# lego-traffic-lights-controller.net
KiCad netlist of a schematic drawn in EAGLE
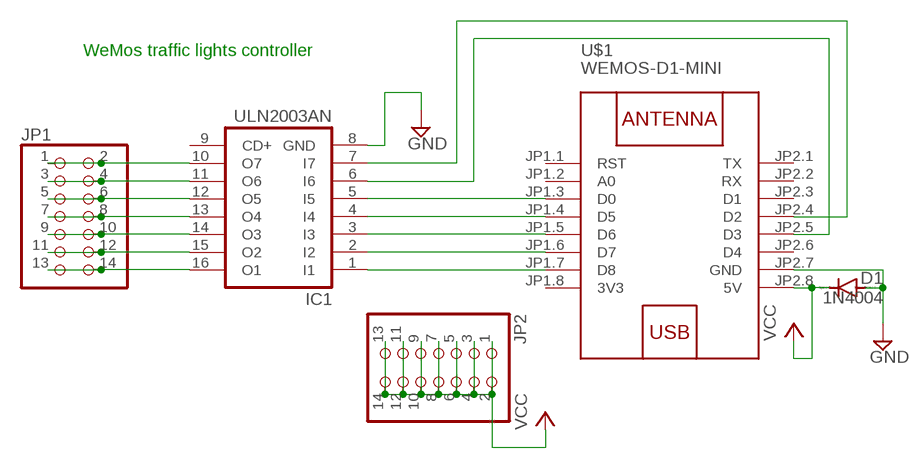
[diagram p0: schematic, sheet 1]

(export (version "E")
  (design (tool "Eeschema 10.0.6"))
  (components
    (comp (ref "D1")
      (value "1N4004")
      (footprint "eagle-import:DO41-10")
      (libsource (lib "eagle-import") (part "1N4004"))
    )
    (comp (ref "IC1")
      (value "ULN2003AN")
      (footprint "eagle-import:DIL16")
      (libsource (lib "eagle-import") (part "ULN2003AN"))
    )
    (comp (ref "JP1")
      (value "PINHD-2X7")
      (footprint "eagle-import:2X07")
      (libsource (lib "eagle-import") (part "PINHD-2X7"))
    )
    (comp (ref "JP2")
      (value "PINHD-2X7")
      (footprint "eagle-import:2X07")
      (libsource (lib "eagle-import") (part "PINHD-2X7"))
    )
    (comp (ref "U$1")
      (value "WEMOS-D1-MINI")
      (footprint "eagle-import:WEMOS-D1-MINI")
      (libsource (lib "eagle-import") (part "WEMOS-D1-MINI"))
    )
  )
  (nets
    (net (code "1") (name "/3V3") (class "Default")
      (node (ref "U$1") (pin "JP1.8") (pinfunction "3V3_JP1.8") (pintype "power_in"))
    )
    (net (code "2") (name "GND") (class "Default")
      (node (ref "D1") (pin "A") (pinfunction "A_A") (pintype "passive"))
      (node (ref "IC1") (pin "8") (pinfunction "GND_8") (pintype "power_in"))
      (node (ref "U$1") (pin "JP2.7") (pinfunction "GND_JP2.7") (pintype "power_in"))
    )
    (net (code "3") (name "Net-(IC1-I1)") (class "Default")
      (node (ref "IC1") (pin "1") (pinfunction "I1_1") (pintype "input"))
      (node (ref "U$1") (pin "JP1.7") (pinfunction "D8_JP1.7") (pintype "bidirectional"))
    )
    (net (code "4") (name "Net-(IC1-I2)") (class "Default")
      (node (ref "IC1") (pin "2") (pinfunction "I2_2") (pintype "input"))
      (node (ref "U$1") (pin "JP1.6") (pinfunction "D7_JP1.6") (pintype "bidirectional"))
    )
    (net (code "5") (name "Net-(IC1-I3)") (class "Default")
      (node (ref "IC1") (pin "3") (pinfunction "I3_3") (pintype "input"))
      (node (ref "U$1") (pin "JP1.5") (pinfunction "D6_JP1.5") (pintype "bidirectional"))
    )
    (net (code "6") (name "Net-(IC1-I4)") (class "Default")
      (node (ref "IC1") (pin "4") (pinfunction "I4_4") (pintype "input"))
      (node (ref "U$1") (pin "JP1.4") (pinfunction "D5_JP1.4") (pintype "bidirectional"))
    )
    (net (code "7") (name "Net-(IC1-I5)") (class "Default")
      (node (ref "IC1") (pin "5") (pinfunction "I5_5") (pintype "input"))
      (node (ref "U$1") (pin "JP1.3") (pinfunction "D0_JP1.3") (pintype "bidirectional"))
    )
    (net (code "8") (name "Net-(IC1-I6)") (class "Default")
      (node (ref "IC1") (pin "6") (pinfunction "I6_6") (pintype "input"))
      (node (ref "U$1") (pin "JP2.5") (pinfunction "D3_JP2.5") (pintype "bidirectional"))
    )
    (net (code "9") (name "Net-(IC1-I7)") (class "Default")
      (node (ref "IC1") (pin "7") (pinfunction "I7_7") (pintype "input"))
      (node (ref "U$1") (pin "JP2.4") (pinfunction "D2_JP2.4") (pintype "bidirectional"))
    )
    (net (code "10") (name "Net-(IC1-O1)") (class "Default")
      (node (ref "IC1") (pin "16") (pinfunction "O1_16") (pintype "open_collector"))
      (node (ref "JP1") (pin "13") (pinfunction "13_13") (pintype "passive"))
      (node (ref "JP1") (pin "14") (pinfunction "14_14") (pintype "passive"))
    )
    (net (code "11") (name "Net-(IC1-O2)") (class "Default")
      (node (ref "IC1") (pin "15") (pinfunction "O2_15") (pintype "open_collector"))
      (node (ref "JP1") (pin "11") (pinfunction "11_11") (pintype "passive"))
      (node (ref "JP1") (pin "12") (pinfunction "12_12") (pintype "passive"))
    )
    (net (code "12") (name "Net-(IC1-O3)") (class "Default")
      (node (ref "IC1") (pin "14") (pinfunction "O3_14") (pintype "open_collector"))
      (node (ref "JP1") (pin "10") (pinfunction "10_10") (pintype "passive"))
      (node (ref "JP1") (pin "9") (pinfunction "9_9") (pintype "passive"))
    )
    (net (code "13") (name "Net-(IC1-O4)") (class "Default")
      (node (ref "IC1") (pin "13") (pinfunction "O4_13") (pintype "open_collector"))
      (node (ref "JP1") (pin "7") (pinfunction "7_7") (pintype "passive"))
      (node (ref "JP1") (pin "8") (pinfunction "8_8") (pintype "passive"))
    )
    (net (code "14") (name "Net-(IC1-O5)") (class "Default")
      (node (ref "IC1") (pin "12") (pinfunction "O5_12") (pintype "open_collector"))
      (node (ref "JP1") (pin "5") (pinfunction "5_5") (pintype "passive"))
      (node (ref "JP1") (pin "6") (pinfunction "6_6") (pintype "passive"))
    )
    (net (code "15") (name "Net-(IC1-O6)") (class "Default")
      (node (ref "IC1") (pin "11") (pinfunction "O6_11") (pintype "open_collector"))
      (node (ref "JP1") (pin "3") (pinfunction "3_3") (pintype "passive"))
      (node (ref "JP1") (pin "4") (pinfunction "4_4") (pintype "passive"))
    )
    (net (code "16") (name "Net-(IC1-O7)") (class "Default")
      (node (ref "IC1") (pin "10") (pinfunction "O7_10") (pintype "open_collector"))
      (node (ref "JP1") (pin "1") (pinfunction "1_1") (pintype "passive"))
      (node (ref "JP1") (pin "2") (pinfunction "2_2") (pintype "passive"))
    )
    (net (code "17") (name "VCC") (class "Default")
      (node (ref "D1") (pin "C") (pinfunction "C_C") (pintype "passive"))
      (node (ref "JP2") (pin "1") (pinfunction "1_1") (pintype "passive"))
      (node (ref "JP2") (pin "10") (pinfunction "10_10") (pintype "passive"))
      (node (ref "JP2") (pin "11") (pinfunction "11_11") (pintype "passive"))
      (node (ref "JP2") (pin "12") (pinfunction "12_12") (pintype "passive"))
      (node (ref "JP2") (pin "13") (pinfunction "13_13") (pintype "passive"))
      (node (ref "JP2") (pin "14") (pinfunction "14_14") (pintype "passive"))
      (node (ref "JP2") (pin "2") (pinfunction "2_2") (pintype "passive"))
      (node (ref "JP2") (pin "3") (pinfunction "3_3") (pintype "passive"))
      (node (ref "JP2") (pin "4") (pinfunction "4_4") (pintype "passive"))
      (node (ref "JP2") (pin "5") (pinfunction "5_5") (pintype "passive"))
      (node (ref "JP2") (pin "6") (pinfunction "6_6") (pintype "passive"))
      (node (ref "JP2") (pin "7") (pinfunction "7_7") (pintype "passive"))
      (node (ref "JP2") (pin "8") (pinfunction "8_8") (pintype "passive"))
      (node (ref "JP2") (pin "9") (pinfunction "9_9") (pintype "passive"))
      (node (ref "U$1") (pin "JP2.8") (pinfunction "5V_JP2.8") (pintype "power_in"))
    )
    (net (code "18") (name "unconnected-(IC1-CD+-Pad9)") (class "Default")
      (node (ref "IC1") (pin "9") (pinfunction "CD+_9") (pintype "passive"))
    )
    (net (code "19") (name "unconnected-(U$1-A0-PadJP1.2)") (class "Default")
      (node (ref "U$1") (pin "JP1.2") (pinfunction "A0_JP1.2") (pintype "bidirectional"))
    )
    (net (code "20") (name "unconnected-(U$1-D1-PadJP2.3)") (class "Default")
      (node (ref "U$1") (pin "JP2.3") (pinfunction "D1_JP2.3") (pintype "bidirectional"))
    )
    (net (code "21") (name "unconnected-(U$1-D4-PadJP2.6)") (class "Default")
      (node (ref "U$1") (pin "JP2.6") (pinfunction "D4_JP2.6") (pintype "bidirectional"))
    )
    (net (code "22") (name "unconnected-(U$1-RST-PadJP1.1)") (class "Default")
      (node (ref "U$1") (pin "JP1.1") (pinfunction "RST_JP1.1") (pintype "bidirectional"))
    )
    (net (code "23") (name "unconnected-(U$1-RX-PadJP2.2)") (class "Default")
      (node (ref "U$1") (pin "JP2.2") (pinfunction "RX_JP2.2") (pintype "bidirectional"))
    )
    (net (code "24") (name "unconnected-(U$1-TX-PadJP2.1)") (class "Default")
      (node (ref "U$1") (pin "JP2.1") (pinfunction "TX_JP2.1") (pintype "bidirectional"))
    )
  )
)
